# szu-etep-stc89c52rc-2024.net
KiCad netlist of a schematic drawn in EasyEDA Pro
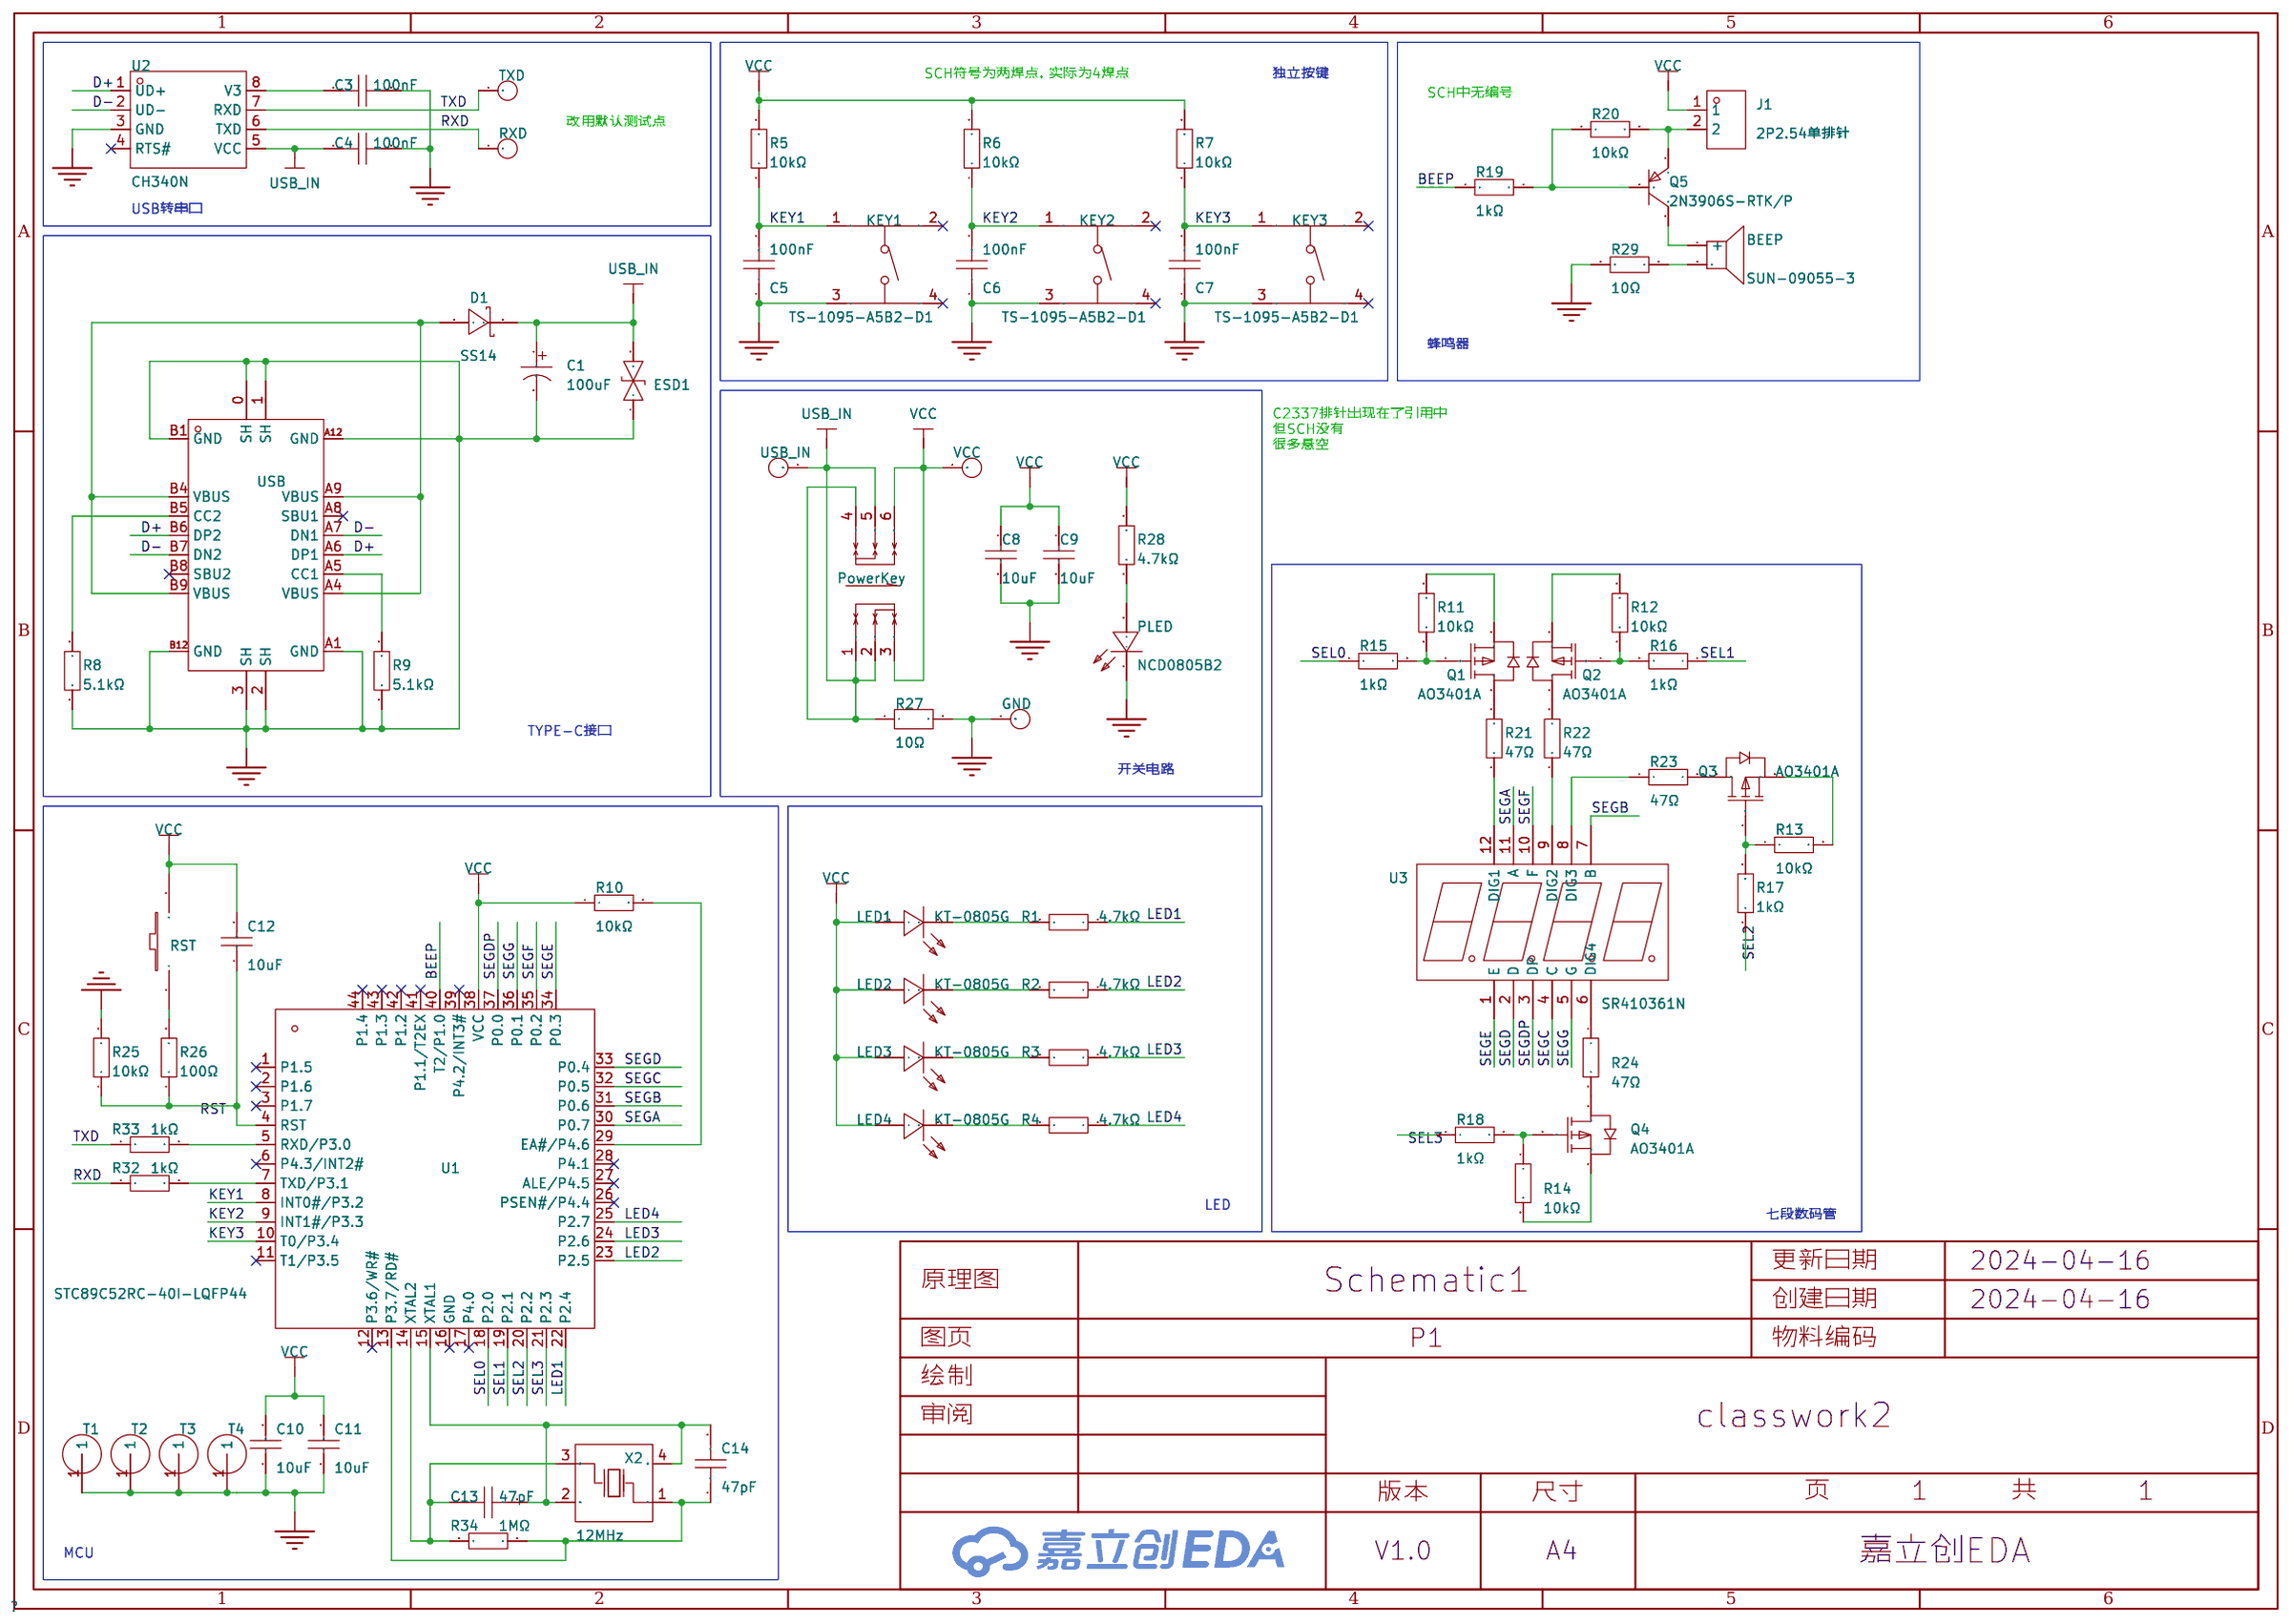
[diagram p0: schematic sheet]

(export (version "E")
  (design (tool "Eeschema 10.0.6"))
  (components
    (comp (ref "BEEP")
      (value "SUN-09055-3")
      (footprint "easyedapro:BUZ-TH_BD9.0-P5.00-D0.6-FD")
      (description "频率2800+300Hz,1.5-5V电压驱动")
      (libsource (lib "easyedapro") (part "SUN-09055-3"))
    )
    (comp (ref "C1")
      (value "100uF")
      (footprint "easyedapro:CAP-TH_BD5.0-P2.00-D0.8-FD")
      (description "容值:100uF;精度:±20%;额定电压:16V;纹波电流:-;等效串联电阻:-;")
      (fields
        (field (name "Manufacturer Part") "KS107M016D07RR0VH2FP0")
        (field (name "Manufacturer") "CX(承兴)")
      )
      (libsource (lib "easyedapro") (part "100uF 16V 5*7"))
    )
    (comp (ref "C3")
      (value "100nF")
      (footprint "easyedapro:C0603")
      (description "容值:100nF;精度:±10%;额定电压:50V;材质(温度系数):X7R;")
      (fields
        (field (name "Manufacturer Part") "CC0603KRX7R9BB104")
        (field (name "Manufacturer") "YAGEO(国巨)")
      )
      (libsource (lib "easyedapro") (part "CC0603KRX7R9BB104"))
    )
    (comp (ref "C4")
      (value "100nF")
      (footprint "easyedapro:C0603")
      (description "容值:100nF;精度:±10%;额定电压:50V;材质(温度系数):X7R;")
      (fields
        (field (name "Manufacturer Part") "CC0603KRX7R9BB104")
        (field (name "Manufacturer") "YAGEO(国巨)")
      )
      (libsource (lib "easyedapro") (part "CC0603KRX7R9BB104"))
    )
    (comp (ref "C5")
      (value "100nF")
      (footprint "easyedapro:C0603")
      (description "容值:100nF;精度:±10%;额定电压:50V;材质(温度系数):X7R;")
      (fields
        (field (name "Manufacturer Part") "CC0603KRX7R9BB104")
        (field (name "Manufacturer") "YAGEO(国巨)")
      )
      (libsource (lib "easyedapro") (part "CC0603KRX7R9BB104"))
    )
    (comp (ref "C6")
      (value "100nF")
      (footprint "easyedapro:C0603")
      (description "容值:100nF;精度:±10%;额定电压:50V;材质(温度系数):X7R;")
      (fields
        (field (name "Manufacturer Part") "CC0603KRX7R9BB104")
        (field (name "Manufacturer") "YAGEO(国巨)")
      )
      (libsource (lib "easyedapro") (part "CC0603KRX7R9BB104"))
    )
    (comp (ref "C7")
      (value "100nF")
      (footprint "easyedapro:C0603")
      (description "容值:100nF;精度:±10%;额定电压:50V;材质(温度系数):X7R;")
      (fields
        (field (name "Manufacturer Part") "CC0603KRX7R9BB104")
        (field (name "Manufacturer") "YAGEO(国巨)")
      )
      (libsource (lib "easyedapro") (part "CC0603KRX7R9BB104"))
    )
    (comp (ref "C8")
      (value "10uF")
      (footprint "easyedapro:C0603")
      (description "容值:10uF;精度:±10%;额定电压:16V;材质(温度系数):X5R;")
      (fields (field (name "Manufacturer Part") "0603X106K160NT") (field (name "Manufacturer") "FH(风华)"))
      (libsource (lib "easyedapro") (part "0603X106K160NT"))
    )
    (comp (ref "C9")
      (value "10uF")
      (footprint "easyedapro:C0603")
      (description "容值:10uF;精度:±10%;额定电压:16V;材质(温度系数):X5R;")
      (fields (field (name "Manufacturer Part") "0603X106K160NT") (field (name "Manufacturer") "FH(风华)"))
      (libsource (lib "easyedapro") (part "0603X106K160NT"))
    )
    (comp (ref "C10")
      (value "10uF")
      (footprint "easyedapro:C0603")
      (description "容值:10uF;精度:±10%;额定电压:16V;材质(温度系数):X5R;")
      (fields (field (name "Manufacturer Part") "0603X106K160NT") (field (name "Manufacturer") "FH(风华)"))
      (libsource (lib "easyedapro") (part "0603X106K160NT"))
    )
    (comp (ref "C11")
      (value "10uF")
      (footprint "easyedapro:C0603")
      (description "容值:10uF;精度:±10%;额定电压:16V;材质(温度系数):X5R;")
      (fields (field (name "Manufacturer Part") "0603X106K160NT") (field (name "Manufacturer") "FH(风华)"))
      (libsource (lib "easyedapro") (part "0603X106K160NT"))
    )
    (comp (ref "C12")
      (value "10uF")
      (footprint "easyedapro:C0603")
      (description "容值:10uF;精度:±10%;额定电压:16V;材质(温度系数):X5R;")
      (fields (field (name "Manufacturer Part") "0603X106K160NT") (field (name "Manufacturer") "FH(风华)"))
      (libsource (lib "easyedapro") (part "0603X106K160NT"))
    )
    (comp (ref "C13")
      (value "47pF")
      (footprint "easyedapro:C0603")
      (description "容值:47pF;精度:±5%;额定电压:100V;材质(温度系数):C0G;")
      (fields
        (field (name "Manufacturer Part") "CL10C470JC8NNNC")
        (field (name "Manufacturer") "SAMSUNG(三星)")
      )
      (libsource (lib "easyedapro") (part "CL10C470JC8NNNC"))
    )
    (comp (ref "C14")
      (value "47pF")
      (footprint "easyedapro:C0603")
      (description "容值:47pF;精度:±5%;额定电压:100V;材质(温度系数):C0G;")
      (fields
        (field (name "Manufacturer Part") "CL10C470JC8NNNC")
        (field (name "Manufacturer") "SAMSUNG(三星)")
      )
      (libsource (lib "easyedapro") (part "CL10C470JC8NNNC"))
    )
    (comp (ref "D1")
      (value "SS14")
      (footprint "easyedapro:SMA_L4.3-W2.6-LS5.2-RD")
      (description "正向压降(Vf):550mV@1A;直流反向耐压(Vr):40V;平均整流电流(Io):1A;")
      (fields (field (name "Manufacturer") "星海"))
      (libsource (lib "easyedapro") (part "SS14_C84343"))
    )
    (comp (ref "ESD1")
      (value "0603ESDA-05N")
      (footprint "easyedapro:D0603-BI")
      (description "极性:双向;反向截止电压(Vrwm):5V;最大钳位电压:50V;")
      (fields (field (name "Manufacturer") "BORN(伯恩半导体)"))
      (libsource (lib "easyedapro") (part "0603ESDA-05N"))
    )
    (comp (ref "GND")
      (value "~")
      (footprint "easyedapro:测试点0.9mm")
      (libsource (lib "easyedapro") (part "测试点0.9mm"))
    )
    (comp (ref "J1")
      (value "2P2.54单排针")
      (footprint "easyedapro:HDR-TH_2P-P2.54-V-M")
      (libsource (lib "easyedapro") (part "2P2.54单排针"))
    )
    (comp (ref "KEY1")
      (value "TS-1095-A5B2-D1")
      (footprint "easyedapro:SW-TH_4P-L6.0-W6.0-P4.50-LS6.5")
      (description "电路结构:单刀单掷;按钮形状:圆形按钮;作用力:180gf;安装方式:直插;开关长度:6mm;开关宽度:6mm;开关高度:6mm;带支架:不带;机械寿命:-;")
      (fields (field (name "Manufacturer") "Yuandi(元迪)"))
      (libsource (lib "easyedapro") (part "TS-1095-A5B2-D1"))
    )
    (comp (ref "KEY2")
      (value "TS-1095-A5B2-D1")
      (footprint "easyedapro:SW-TH_4P-L6.0-W6.0-P4.50-LS6.5")
      (description "电路结构:单刀单掷;按钮形状:圆形按钮;作用力:180gf;安装方式:直插;开关长度:6mm;开关宽度:6mm;开关高度:6mm;带支架:不带;机械寿命:-;")
      (fields (field (name "Manufacturer") "Yuandi(元迪)"))
      (libsource (lib "easyedapro") (part "TS-1095-A5B2-D1"))
    )
    (comp (ref "KEY3")
      (value "TS-1095-A5B2-D1")
      (footprint "easyedapro:SW-TH_4P-L6.0-W6.0-P4.50-LS6.5")
      (description "电路结构:单刀单掷;按钮形状:圆形按钮;作用力:180gf;安装方式:直插;开关长度:6mm;开关宽度:6mm;开关高度:6mm;带支架:不带;机械寿命:-;")
      (fields (field (name "Manufacturer") "Yuandi(元迪)"))
      (libsource (lib "easyedapro") (part "TS-1095-A5B2-D1"))
    )
    (comp (ref "LED1")
      (value "KT-0805G")
      (footprint "easyedapro:LED0805-R-RD")
      (description "灯头类型:-;发光颜色:翠绿色;正向电压(VF):-;功率:-;正向电流:-;主波长:-;二极管配置:-;透镜颜色:-;色温:-;发光强度:-;发光角度:-;载带方式:-;工作温度:-;")
      (fields (field (name "Manufacturer") "KENTO"))
      (libsource (lib "easyedapro") (part "0805G (Green)"))
    )
    (comp (ref "LED2")
      (value "KT-0805G")
      (footprint "easyedapro:LED0805-R-RD")
      (description "灯头类型:-;发光颜色:翠绿色;正向电压(VF):-;功率:-;正向电流:-;主波长:-;二极管配置:-;透镜颜色:-;色温:-;发光强度:-;发光角度:-;载带方式:-;工作温度:-;")
      (fields (field (name "Manufacturer") "KENTO"))
      (libsource (lib "easyedapro") (part "0805G (Green)"))
    )
    (comp (ref "LED3")
      (value "KT-0805G")
      (footprint "easyedapro:LED0805-R-RD")
      (description "灯头类型:-;发光颜色:翠绿色;正向电压(VF):-;功率:-;正向电流:-;主波长:-;二极管配置:-;透镜颜色:-;色温:-;发光强度:-;发光角度:-;载带方式:-;工作温度:-;")
      (fields (field (name "Manufacturer") "KENTO"))
      (libsource (lib "easyedapro") (part "0805G (Green)"))
    )
    (comp (ref "LED4")
      (value "KT-0805G")
      (footprint "easyedapro:LED0805-R-RD")
      (description "灯头类型:-;发光颜色:翠绿色;正向电压(VF):-;功率:-;正向电流:-;主波长:-;二极管配置:-;透镜颜色:-;色温:-;发光强度:-;发光角度:-;载带方式:-;工作温度:-;")
      (fields (field (name "Manufacturer") "KENTO"))
      (libsource (lib "easyedapro") (part "0805G (Green)"))
    )
    (comp (ref "PLED")
      (value "NCD0805B2")
      (footprint "easyedapro:LED0805-R-RD")
      (fields (field (name "Manufacturer") "国星光电"))
      (libsource (lib "easyedapro") (part "FC-A2012BK-470H2"))
    )
    (comp (ref "PowerKey")
      (value "XKB8080-Z")
      (footprint "easyedapro:SW-TH_6P-L8.0-W8.0-P2.50")
      (description "自锁/无锁:自锁;安装方式:直插;触点电流:100mA;额定电压 (AC):250V;额定电压 (DC):30V;带灯:不带;作用力:160gf;机械寿命:10万次;")
      (fields (field (name "Manufacturer") "XKB Connectivity(中国星坤)"))
      (libsource (lib "easyedapro") (part "XKB8080-Z"))
    )
    (comp (ref "Q1")
      (value "AO3401A")
      (footprint "easyedapro:SOT-23_L2.9-W1.3-P1.90-LS2.4-BR")
      (fields (field (name "Manufacturer") "AOS"))
      (libsource (lib "easyedapro") (part "AO3401A"))
    )
    (comp (ref "Q2")
      (value "AO3401A")
      (footprint "easyedapro:SOT-23_L2.9-W1.3-P1.90-LS2.4-BR")
      (fields (field (name "Manufacturer") "AOS"))
      (libsource (lib "easyedapro") (part "AO3401A"))
    )
    (comp (ref "Q3")
      (value "AO3401A")
      (footprint "easyedapro:SOT-23_L2.9-W1.3-P1.90-LS2.4-BR")
      (fields (field (name "Manufacturer") "AOS"))
      (libsource (lib "easyedapro") (part "AO3401A"))
    )
    (comp (ref "Q4")
      (value "AO3401A")
      (footprint "easyedapro:SOT-23_L2.9-W1.3-P1.90-LS2.4-BR")
      (fields (field (name "Manufacturer") "AOS"))
      (libsource (lib "easyedapro") (part "AO3401A"))
    )
    (comp (ref "Q5")
      (value "2N3906S-RTK/P")
      (footprint "easyedapro:SOT-23-3_L2.9-W1.6-P1.90-LS2.8-TR-CW")
      (description "晶体管类型:PNP;集电极电流(Ic):200mA;集射极击穿电压(Vceo):40V;功率(Pd):350mW;直流电流增益(hFE@Ic,Vce):100@10mA,1V;")
      (fields (field (name "Manufacturer") "KEC"))
      (libsource (lib "easyedapro") (part "2N3906S-RTK/PS"))
    )
    (comp (ref "R1")
      (value "4.7kΩ")
      (footprint "easyedapro:R0603")
      (description "电阻类型:厚膜电阻;阻值:4.7kΩ;精度:±1%;功率:100mW;最大工作电压:75V;温度系数:±100ppm/°C;")
      (fields
        (field (name "Manufacturer Part") "0603WAF4701T5E")
        (field (name "Manufacturer") "UNI-ROYAL(厚声)")
      )
      (libsource (lib "easyedapro") (part "0603WAF4701T5E"))
    )
    (comp (ref "R2")
      (value "4.7kΩ")
      (footprint "easyedapro:R0603")
      (description "电阻类型:厚膜电阻;阻值:4.7kΩ;精度:±1%;功率:100mW;最大工作电压:75V;温度系数:±100ppm/°C;")
      (fields
        (field (name "Manufacturer Part") "0603WAF4701T5E")
        (field (name "Manufacturer") "UNI-ROYAL(厚声)")
      )
      (libsource (lib "easyedapro") (part "0603WAF4701T5E"))
    )
    (comp (ref "R3")
      (value "4.7kΩ")
      (footprint "easyedapro:R0603")
      (description "电阻类型:厚膜电阻;阻值:4.7kΩ;精度:±1%;功率:100mW;最大工作电压:75V;温度系数:±100ppm/°C;")
      (fields
        (field (name "Manufacturer Part") "0603WAF4701T5E")
        (field (name "Manufacturer") "UNI-ROYAL(厚声)")
      )
      (libsource (lib "easyedapro") (part "0603WAF4701T5E"))
    )
    (comp (ref "R4")
      (value "4.7kΩ")
      (footprint "easyedapro:R0603")
      (description "电阻类型:厚膜电阻;阻值:4.7kΩ;精度:±1%;功率:100mW;最大工作电压:75V;温度系数:±100ppm/°C;")
      (fields
        (field (name "Manufacturer Part") "0603WAF4701T5E")
        (field (name "Manufacturer") "UNI-ROYAL(厚声)")
      )
      (libsource (lib "easyedapro") (part "0603WAF4701T5E"))
    )
    (comp (ref "R5")
      (value "10kΩ")
      (footprint "easyedapro:R0402")
      (description "电阻类型:厚膜电阻;阻值:10kΩ;精度:±1%;功率:62.5mW;最大工作电压:50V;温度系数:±100ppm/°C;")
      (fields
        (field (name "Manufacturer Part") "0402WGF1002TCE")
        (field (name "Manufacturer") "UNI-ROYAL(厚声)")
      )
      (libsource (lib "easyedapro") (part "0402WGF1002TCE"))
    )
    (comp (ref "R6")
      (value "10kΩ")
      (footprint "easyedapro:R0402")
      (description "电阻类型:厚膜电阻;阻值:10kΩ;精度:±1%;功率:62.5mW;最大工作电压:50V;温度系数:±100ppm/°C;")
      (fields
        (field (name "Manufacturer Part") "0402WGF1002TCE")
        (field (name "Manufacturer") "UNI-ROYAL(厚声)")
      )
      (libsource (lib "easyedapro") (part "0402WGF1002TCE"))
    )
    (comp (ref "R7")
      (value "10kΩ")
      (footprint "easyedapro:R0402")
      (description "电阻类型:厚膜电阻;阻值:10kΩ;精度:±1%;功率:62.5mW;最大工作电压:50V;温度系数:±100ppm/°C;")
      (fields
        (field (name "Manufacturer Part") "0402WGF1002TCE")
        (field (name "Manufacturer") "UNI-ROYAL(厚声)")
      )
      (libsource (lib "easyedapro") (part "0402WGF1002TCE"))
    )
    (comp (ref "R8")
      (value "5.1kΩ")
      (footprint "easyedapro:R0603")
      (description "电阻类型:厚膜电阻;阻值:5.1kΩ;精度:±1%;功率:100mW;最大工作电压:75V;温度系数:±100ppm/°C;")
      (fields
        (field (name "Manufacturer Part") "0603WAF5101T5E")
        (field (name "Manufacturer") "UNI-ROYAL(厚声)")
      )
      (libsource (lib "easyedapro") (part "0603WAF5101T5E"))
    )
    (comp (ref "R9")
      (value "5.1kΩ")
      (footprint "easyedapro:R0603")
      (description "电阻类型:厚膜电阻;阻值:5.1kΩ;精度:±1%;功率:100mW;最大工作电压:75V;温度系数:±100ppm/°C;")
      (fields
        (field (name "Manufacturer Part") "0603WAF5101T5E")
        (field (name "Manufacturer") "UNI-ROYAL(厚声)")
      )
      (libsource (lib "easyedapro") (part "0603WAF5101T5E"))
    )
    (comp (ref "R10")
      (value "10kΩ")
      (footprint "easyedapro:R0402")
      (description "电阻类型:厚膜电阻;阻值:10kΩ;精度:±1%;功率:62.5mW;最大工作电压:50V;温度系数:±100ppm/°C;")
      (fields
        (field (name "Manufacturer Part") "0402WGF1002TCE")
        (field (name "Manufacturer") "UNI-ROYAL(厚声)")
      )
      (libsource (lib "easyedapro") (part "0402WGF1002TCE"))
    )
    (comp (ref "R11")
      (value "10kΩ")
      (footprint "easyedapro:R0603")
      (description "电阻类型:厚膜电阻;阻值:10kΩ;精度:±1%;功率:100mW;最大工作电压:75V;温度系数:±100ppm/°C;")
      (fields
        (field (name "Manufacturer Part") "0603WAF1002T5E")
        (field (name "Manufacturer") "UNI-ROYAL(厚声)")
      )
      (libsource (lib "easyedapro") (part "0603WAF1002T5E"))
    )
    (comp (ref "R12")
      (value "10kΩ")
      (footprint "easyedapro:R0603")
      (description "电阻类型:厚膜电阻;阻值:10kΩ;精度:±1%;功率:100mW;最大工作电压:75V;温度系数:±100ppm/°C;")
      (fields
        (field (name "Manufacturer Part") "0603WAF1002T5E")
        (field (name "Manufacturer") "UNI-ROYAL(厚声)")
      )
      (libsource (lib "easyedapro") (part "0603WAF1002T5E"))
    )
    (comp (ref "R13")
      (value "10kΩ")
      (footprint "easyedapro:R0603")
      (description "电阻类型:厚膜电阻;阻值:10kΩ;精度:±1%;功率:100mW;最大工作电压:75V;温度系数:±100ppm/°C;")
      (fields
        (field (name "Manufacturer Part") "0603WAF1002T5E")
        (field (name "Manufacturer") "UNI-ROYAL(厚声)")
      )
      (libsource (lib "easyedapro") (part "0603WAF1002T5E"))
    )
    (comp (ref "R14")
      (value "10kΩ")
      (footprint "easyedapro:R0603")
      (description "电阻类型:厚膜电阻;阻值:10kΩ;精度:±1%;功率:100mW;最大工作电压:75V;温度系数:±100ppm/°C;")
      (fields
        (field (name "Manufacturer Part") "0603WAF1002T5E")
        (field (name "Manufacturer") "UNI-ROYAL(厚声)")
      )
      (libsource (lib "easyedapro") (part "0603WAF1002T5E"))
    )
    (comp (ref "R15")
      (value "1kΩ")
      (footprint "easyedapro:R0603")
      (description "电阻类型:厚膜电阻;阻值:1kΩ;精度:±1%;功率:100mW;最大工作电压:75V;温度系数:±100ppm/°C;")
      (fields
        (field (name "Manufacturer Part") "0603WAF1001T5E")
        (field (name "Manufacturer") "UNI-ROYAL(厚声)")
      )
      (libsource (lib "easyedapro") (part "0603WAF1001T5E"))
    )
    (comp (ref "R16")
      (value "1kΩ")
      (footprint "easyedapro:R0603")
      (description "电阻类型:厚膜电阻;阻值:1kΩ;精度:±1%;功率:100mW;最大工作电压:75V;温度系数:±100ppm/°C;")
      (fields
        (field (name "Manufacturer Part") "0603WAF1001T5E")
        (field (name "Manufacturer") "UNI-ROYAL(厚声)")
      )
      (libsource (lib "easyedapro") (part "0603WAF1001T5E"))
    )
    (comp (ref "R17")
      (value "1kΩ")
      (footprint "easyedapro:R0603")
      (description "电阻类型:厚膜电阻;阻值:1kΩ;精度:±1%;功率:100mW;最大工作电压:75V;温度系数:±100ppm/°C;")
      (fields
        (field (name "Manufacturer Part") "0603WAF1001T5E")
        (field (name "Manufacturer") "UNI-ROYAL(厚声)")
      )
      (libsource (lib "easyedapro") (part "0603WAF1001T5E"))
    )
    (comp (ref "R18")
      (value "1kΩ")
      (footprint "easyedapro:R0603")
      (description "电阻类型:厚膜电阻;阻值:1kΩ;精度:±1%;功率:100mW;最大工作电压:75V;温度系数:±100ppm/°C;")
      (fields
        (field (name "Manufacturer Part") "0603WAF1001T5E")
        (field (name "Manufacturer") "UNI-ROYAL(厚声)")
      )
      (libsource (lib "easyedapro") (part "0603WAF1001T5E"))
    )
    (comp (ref "R19")
      (value "1kΩ")
      (footprint "easyedapro:R0603")
      (description "电阻类型:厚膜电阻;阻值:1kΩ;精度:±1%;功率:100mW;最大工作电压:75V;温度系数:±100ppm/°C;")
      (fields
        (field (name "Manufacturer Part") "0603WAF1001T5E")
        (field (name "Manufacturer") "UNI-ROYAL(厚声)")
      )
      (libsource (lib "easyedapro") (part "0603WAF1001T5E"))
    )
    (comp (ref "R20")
      (value "10kΩ")
      (footprint "easyedapro:R0603")
      (description "电阻类型:厚膜电阻;阻值:10kΩ;精度:±1%;功率:100mW;最大工作电压:75V;温度系数:±100ppm/°C;")
      (fields
        (field (name "Manufacturer Part") "0603WAF1002T5E")
        (field (name "Manufacturer") "UNI-ROYAL(厚声)")
      )
      (libsource (lib "easyedapro") (part "0603WAF1002T5E"))
    )
    (comp (ref "R21")
      (value "47Ω")
      (footprint "easyedapro:R0603")
      (description "电阻类型:厚膜电阻;阻值:47Ω;精度:±1%;功率:100mW;最大工作电压:75V;温度系数:±100ppm/°C;")
      (fields
        (field (name "Manufacturer Part") "0603WAF470JT5E")
        (field (name "Manufacturer") "UNI-ROYAL(厚声)")
      )
      (libsource (lib "easyedapro") (part "0603WAF470JT5E"))
    )
    (comp (ref "R22")
      (value "47Ω")
      (footprint "easyedapro:R0603")
      (description "电阻类型:厚膜电阻;阻值:47Ω;精度:±1%;功率:100mW;最大工作电压:75V;温度系数:±100ppm/°C;")
      (fields
        (field (name "Manufacturer Part") "0603WAF470JT5E")
        (field (name "Manufacturer") "UNI-ROYAL(厚声)")
      )
      (libsource (lib "easyedapro") (part "0603WAF470JT5E"))
    )
    (comp (ref "R23")
      (value "47Ω")
      (footprint "easyedapro:R0603")
      (description "电阻类型:厚膜电阻;阻值:47Ω;精度:±1%;功率:100mW;最大工作电压:75V;温度系数:±100ppm/°C;")
      (fields
        (field (name "Manufacturer Part") "0603WAF470JT5E")
        (field (name "Manufacturer") "UNI-ROYAL(厚声)")
      )
      (libsource (lib "easyedapro") (part "0603WAF470JT5E"))
    )
    (comp (ref "R24")
      (value "47Ω")
      (footprint "easyedapro:R0603")
      (description "电阻类型:厚膜电阻;阻值:47Ω;精度:±1%;功率:100mW;最大工作电压:75V;温度系数:±100ppm/°C;")
      (fields
        (field (name "Manufacturer Part") "0603WAF470JT5E")
        (field (name "Manufacturer") "UNI-ROYAL(厚声)")
      )
      (libsource (lib "easyedapro") (part "0603WAF470JT5E"))
    )
    (comp (ref "R25")
      (value "10kΩ")
      (footprint "easyedapro:R0402")
      (description "电阻类型:厚膜电阻;阻值:10kΩ;精度:±1%;功率:62.5mW;最大工作电压:50V;温度系数:±100ppm/°C;")
      (fields
        (field (name "Manufacturer Part") "0402WGF1002TCE")
        (field (name "Manufacturer") "UNI-ROYAL(厚声)")
      )
      (libsource (lib "easyedapro") (part "0402WGF1002TCE"))
    )
    (comp (ref "R26")
      (value "100Ω")
      (footprint "easyedapro:R0603")
      (description "电阻类型:厚膜电阻;阻值:100Ω;精度:±1%;功率:100mW;最大工作电压:75V;温度系数:±200ppm/°C;")
      (fields
        (field (name "Manufacturer Part") "0603WAF1000T5E")
        (field (name "Manufacturer") "UNI-ROYAL(厚声)")
      )
      (libsource (lib "easyedapro") (part "0603WAF1000T5E"))
    )
    (comp (ref "R27")
      (value "10Ω")
      (footprint "easyedapro:R1206")
      (description "电阻类型:厚膜电阻;阻值:10Ω;精度:±10%;功率:600mW;最大工作电压:200V;温度系数:±400ppm/°C;")
      (fields
        (field (name "Manufacturer Part") "AS0606K0100T5E")
        (field (name "Manufacturer") "UNI-ROYAL(厚声)")
      )
      (libsource (lib "easyedapro") (part "AS0606K0100T5E"))
    )
    (comp (ref "R28")
      (value "4.7kΩ")
      (footprint "easyedapro:R0603")
      (description "电阻类型:厚膜电阻;阻值:4.7kΩ;精度:±1%;功率:100mW;最大工作电压:75V;温度系数:±100ppm/°C;")
      (fields
        (field (name "Manufacturer Part") "0603WAF4701T5E")
        (field (name "Manufacturer") "UNI-ROYAL(厚声)")
      )
      (libsource (lib "easyedapro") (part "0603WAF4701T5E"))
    )
    (comp (ref "R29")
      (value "10Ω")
      (footprint "easyedapro:R0603")
      (description "电阻类型:厚膜电阻;阻值:10Ω;精度:±1%;功率:100mW;最大工作电压:75V;温度系数:±400ppm/°C;")
      (fields
        (field (name "Manufacturer Part") "0603WAF100JT5E")
        (field (name "Manufacturer") "UNI-ROYAL(厚声)")
      )
      (libsource (lib "easyedapro") (part "0603WAF100JT5E"))
    )
    (comp (ref "R32")
      (value "1kΩ")
      (footprint "easyedapro:R0603")
      (description "电阻类型:厚膜电阻;阻值:1kΩ;精度:±1%;功率:100mW;最大工作电压:75V;温度系数:±100ppm/°C;")
      (fields
        (field (name "Manufacturer Part") "0603WAF1001T5E")
        (field (name "Manufacturer") "UNI-ROYAL(厚声)")
      )
      (libsource (lib "easyedapro") (part "0603WAF1001T5E"))
    )
    (comp (ref "R33")
      (value "1kΩ")
      (footprint "easyedapro:R0603")
      (description "电阻类型:厚膜电阻;阻值:1kΩ;精度:±1%;功率:100mW;最大工作电压:75V;温度系数:±100ppm/°C;")
      (fields
        (field (name "Manufacturer Part") "0603WAF1001T5E")
        (field (name "Manufacturer") "UNI-ROYAL(厚声)")
      )
      (libsource (lib "easyedapro") (part "0603WAF1001T5E"))
    )
    (comp (ref "R34")
      (value "1MΩ")
      (footprint "easyedapro:R0603")
      (description "电阻类型:厚膜电阻;阻值:1MΩ;精度:±1%;功率:100mW;最大工作电压:75V;温度系数:±100ppm/°C;")
      (fields
        (field (name "Manufacturer Part") "0603WAF1004T5E")
        (field (name "Manufacturer") "UNI-ROYAL(厚声)")
      )
      (libsource (lib "easyedapro") (part "0603WAF1004T5E"))
    )
    (comp (ref "RST")
      (value "轻触开关,3*6*2.5塑头白色,260G,行程0.25mm,贴片 (SMT业务专用)")
      (footprint "easyedapro:SW-SMD_L6.1-W3.6-LS8.0")
      (libsource (lib "easyedapro") (part "Switch,3*6*2.5Plastic head white,260G, 0.25mm,SMD"))
    )
    (comp (ref "RXD")
      (value "~")
      (footprint "easyedapro:测试点0.9mm")
      (libsource (lib "easyedapro") (part "测试点0.9mm"))
    )
    (comp (ref "T1") (value "~") (footprint "easyedapro:M3定位孔") (libsource (lib "easyedapro") (part "M3定位孔")))
    (comp (ref "T2") (value "~") (footprint "easyedapro:M3定位孔") (libsource (lib "easyedapro") (part "M3定位孔")))
    (comp (ref "T3") (value "~") (footprint "easyedapro:M3定位孔") (libsource (lib "easyedapro") (part "M3定位孔")))
    (comp (ref "T4") (value "~") (footprint "easyedapro:M3定位孔") (libsource (lib "easyedapro") (part "M3定位孔")))
    (comp (ref "TXD")
      (value "~")
      (footprint "easyedapro:测试点0.9mm")
      (libsource (lib "easyedapro") (part "测试点0.9mm"))
    )
    (comp (ref "U1")
      (value "STC89C52RC-40I-LQFP44")
      (footprint "easyedapro:LQFP-44_L10.0-W10.0-P0.80-LS12.0-BL")
      (description "CPU内核:51系列;程序存储容量:8KB;RAM总容量:512Byte;GPIO端口数量:39;工作电压范围:3.3V~5.5V;CPU最大主频:-;程序存储器类型:FLASH;")
      (fields (field (name "Manufacturer") "STC(宏晶)"))
      (libsource (lib "easyedapro") (part "STC89C52RC-40I_C8707"))
    )
    (comp (ref "U2")
      (value "CH340N")
      (footprint "easyedapro:SOP-8_L5.0-W4.0-P1.27-LS6.0-BL")
      (description "应用功能:-;接口协议:-;")
      (fields (field (name "Manufacturer") "WCH(南京沁恒)"))
      (libsource (lib "easyedapro") (part "CH340N"))
    )
    (comp (ref "U3")
      (value "SR410361N")
      (footprint "easyedapro:LED-SEG-TH_12P-L30.0-W14.0-P2.54-S10.26-BL")
      (description "数码管位数:4位;发光颜色:红色;LED极性:共阳极;数字/字母大小(英寸):0.36;")
      (fields (field (name "Manufacturer") "ARKLED(方舟)"))
      (libsource (lib "easyedapro") (part "SR410361N"))
    )
    (comp (ref "USB")
      (value "TYPE-C-31-M-12")
      (footprint "easyedapro:USB-C_SMD-TYPE-C-31-M-12")
      (description "连接器类型:Type-C;标准:-;公母:母;端口数量:1;触点数量:16P;安装方式:-;额定电流 - 电源:5A;触头材质:-;触头镀层:-;工作温度范围:-;焊接温度(最大值):-;")
      (fields (field (name "Manufacturer") "韩国韩荣"))
      (libsource (lib "easyedapro") (part "TYPE-C-31-M-12"))
    )
    (comp (ref "USB_IN")
      (value "~")
      (footprint "easyedapro:测试点0.9mm")
      (libsource (lib "easyedapro") (part "测试点0.9mm"))
    )
    (comp (ref "VCC")
      (value "~")
      (footprint "easyedapro:测试点0.9mm")
      (libsource (lib "easyedapro") (part "测试点0.9mm"))
    )
    (comp (ref "X2")
      (value "12MHz")
      (footprint "easyedapro:OSC-SMD_4P-L3.2-W2.5-BL")
      (description "晶振类型:贴片晶振;频率:12MHz;常温频差:±10ppm;外接负载电容:20pF;频率稳定度(全温):±20ppm;")
      (fields (field (name "Manufacturer Part") "X322512MSB4SI") (field (name "Manufacturer") "YXC(扬兴晶振)"))
      (libsource (lib "easyedapro") (part "X322512MSB4SI"))
    )
  )
  (nets
    (net (code "1") (name "/BEEP") (class "Default")
      (node (ref "R19") (pin "1") (pinfunction "1_1") (pintype "input"))
      (node (ref "U1") (pin "40") (pinfunction "T2/P1.0_40") (pintype "unspecified"))
    )
    (net (code "2") (name "/D+") (class "Default")
      (node (ref "U2") (pin "1") (pinfunction "UD+_1") (pintype "unspecified"))
      (node (ref "USB") (pin "A6") (pinfunction "DP1_A6") (pintype "unspecified"))
      (node (ref "USB") (pin "B6") (pinfunction "DP2_B6") (pintype "unspecified"))
    )
    (net (code "3") (name "/D-") (class "Default")
      (node (ref "U2") (pin "2") (pinfunction "UD-_2") (pintype "unspecified"))
      (node (ref "USB") (pin "A7") (pinfunction "DN1_A7") (pintype "unspecified"))
      (node (ref "USB") (pin "B7") (pinfunction "DN2_B7") (pintype "unspecified"))
    )
    (net (code "4") (name "/KEY1") (class "Default")
      (node (ref "C5") (pin "2") (pinfunction "2_2") (pintype "unspecified"))
      (node (ref "KEY1") (pin "1") (pinfunction "1_1") (pintype "input"))
      (node (ref "R5") (pin "1") (pinfunction "1_1") (pintype "input"))
      (node (ref "U1") (pin "8") (pinfunction "INT0#/P3.2_8") (pintype "unspecified"))
    )
    (net (code "5") (name "/KEY2") (class "Default")
      (node (ref "C6") (pin "2") (pinfunction "2_2") (pintype "unspecified"))
      (node (ref "KEY2") (pin "1") (pinfunction "1_1") (pintype "input"))
      (node (ref "R6") (pin "1") (pinfunction "1_1") (pintype "input"))
      (node (ref "U1") (pin "9") (pinfunction "INT1#/P3.3_9") (pintype "unspecified"))
    )
    (net (code "6") (name "/KEY3") (class "Default")
      (node (ref "C7") (pin "2") (pinfunction "2_2") (pintype "unspecified"))
      (node (ref "KEY3") (pin "1") (pinfunction "1_1") (pintype "input"))
      (node (ref "R7") (pin "1") (pinfunction "1_1") (pintype "input"))
      (node (ref "U1") (pin "10") (pinfunction "T0/P3.4_10") (pintype "unspecified"))
    )
    (net (code "7") (name "/LED1") (class "Default")
      (node (ref "R1") (pin "1") (pinfunction "1_1") (pintype "input"))
      (node (ref "U1") (pin "22") (pinfunction "P2.4_22") (pintype "unspecified"))
    )
    (net (code "8") (name "/LED2") (class "Default")
      (node (ref "R2") (pin "1") (pinfunction "1_1") (pintype "input"))
      (node (ref "U1") (pin "23") (pinfunction "P2.5_23") (pintype "unspecified"))
    )
    (net (code "9") (name "/LED3") (class "Default")
      (node (ref "R3") (pin "1") (pinfunction "1_1") (pintype "input"))
      (node (ref "U1") (pin "24") (pinfunction "P2.6_24") (pintype "unspecified"))
    )
    (net (code "10") (name "/LED4") (class "Default")
      (node (ref "R4") (pin "1") (pinfunction "1_1") (pintype "input"))
      (node (ref "U1") (pin "25") (pinfunction "P2.7_25") (pintype "unspecified"))
    )
    (net (code "11") (name "/RST") (class "Default")
      (node (ref "C12") (pin "1") (pinfunction "1_1") (pintype "input"))
      (node (ref "R25") (pin "1") (pinfunction "1_1") (pintype "input"))
      (node (ref "R26") (pin "1") (pinfunction "1_1") (pintype "input"))
      (node (ref "U1") (pin "4") (pinfunction "RST_4") (pintype "unspecified"))
    )
    (net (code "12") (name "/RXD") (class "Default")
      (node (ref "R32") (pin "1") (pinfunction "1_1") (pintype "input"))
      (node (ref "RXD") (pin "1") (pinfunction "Pin1_1") (pintype "input"))
      (node (ref "U2") (pin "6") (pinfunction "TXD_6") (pintype "unspecified"))
    )
    (net (code "13") (name "/SEGA") (class "Default")
      (node (ref "U1") (pin "30") (pinfunction "P0.7_30") (pintype "unspecified"))
      (node (ref "U3") (pin "11") (pinfunction "A_11") (pintype "input"))
    )
    (net (code "14") (name "/SEGB") (class "Default")
      (node (ref "U1") (pin "31") (pinfunction "P0.6_31") (pintype "unspecified"))
      (node (ref "U3") (pin "7") (pinfunction "B_7") (pintype "input"))
    )
    (net (code "15") (name "/SEGC") (class "Default")
      (node (ref "U1") (pin "32") (pinfunction "P0.5_32") (pintype "unspecified"))
      (node (ref "U3") (pin "4") (pinfunction "C_4") (pintype "input"))
    )
    (net (code "16") (name "/SEGD") (class "Default")
      (node (ref "U1") (pin "33") (pinfunction "P0.4_33") (pintype "unspecified"))
      (node (ref "U3") (pin "2") (pinfunction "D_2") (pintype "input"))
    )
    (net (code "17") (name "/SEGDP") (class "Default")
      (node (ref "U1") (pin "37") (pinfunction "P0.0_37") (pintype "unspecified"))
      (node (ref "U3") (pin "3") (pinfunction "DP_3") (pintype "input"))
    )
    (net (code "18") (name "/SEGE") (class "Default")
      (node (ref "U1") (pin "34") (pinfunction "P0.3_34") (pintype "unspecified"))
      (node (ref "U3") (pin "1") (pinfunction "E_1") (pintype "input"))
    )
    (net (code "19") (name "/SEGF") (class "Default")
      (node (ref "U1") (pin "35") (pinfunction "P0.2_35") (pintype "unspecified"))
      (node (ref "U3") (pin "10") (pinfunction "F_10") (pintype "input"))
    )
    (net (code "20") (name "/SEGG") (class "Default")
      (node (ref "U1") (pin "36") (pinfunction "P0.1_36") (pintype "unspecified"))
      (node (ref "U3") (pin "5") (pinfunction "G_5") (pintype "input"))
    )
    (net (code "21") (name "/SEL0") (class "Default")
      (node (ref "R15") (pin "1") (pinfunction "1_1") (pintype "input"))
      (node (ref "U1") (pin "18") (pinfunction "P2.0_18") (pintype "unspecified"))
    )
    (net (code "22") (name "/SEL1") (class "Default")
      (node (ref "R16") (pin "1") (pinfunction "1_1") (pintype "input"))
      (node (ref "U1") (pin "19") (pinfunction "P2.1_19") (pintype "unspecified"))
    )
    (net (code "23") (name "/SEL2") (class "Default")
      (node (ref "R17") (pin "1") (pinfunction "1_1") (pintype "input"))
      (node (ref "U1") (pin "20") (pinfunction "P2.2_20") (pintype "unspecified"))
    )
    (net (code "24") (name "/SEL3") (class "Default")
      (node (ref "R18") (pin "1") (pinfunction "1_1") (pintype "input"))
      (node (ref "U1") (pin "21") (pinfunction "P2.3_21") (pintype "unspecified"))
    )
    (net (code "25") (name "/TXD") (class "Default")
      (node (ref "R33") (pin "1") (pinfunction "1_1") (pintype "input"))
      (node (ref "TXD") (pin "1") (pinfunction "Pin1_1") (pintype "input"))
      (node (ref "U2") (pin "7") (pinfunction "RXD_7") (pintype "unspecified"))
    )
    (net (code "26") (name "GND") (class "Default")
      (node (ref "C1") (pin "2") (pinfunction "2_2") (pintype "input"))
      (node (ref "C10") (pin "2") (pinfunction "2_2") (pintype "input"))
      (node (ref "C11") (pin "2") (pinfunction "2_2") (pintype "input"))
      (node (ref "C3") (pin "2") (pinfunction "2_2") (pintype "unspecified"))
      (node (ref "C4") (pin "2") (pinfunction "2_2") (pintype "unspecified"))
      (node (ref "C5") (pin "1") (pinfunction "1_1") (pintype "unspecified"))
      (node (ref "C6") (pin "1") (pinfunction "1_1") (pintype "unspecified"))
      (node (ref "C7") (pin "1") (pinfunction "1_1") (pintype "unspecified"))
      (node (ref "C8") (pin "2") (pinfunction "2_2") (pintype "input"))
      (node (ref "C9") (pin "2") (pinfunction "2_2") (pintype "input"))
      (node (ref "ESD1") (pin "1") (pinfunction "1_1") (pintype "unspecified"))
      (node (ref "GND") (pin "1") (pinfunction "Pin1_1") (pintype "input"))
      (node (ref "KEY1") (pin "3") (pinfunction "3_3") (pintype "input"))
      (node (ref "KEY2") (pin "3") (pinfunction "3_3") (pintype "input"))
      (node (ref "KEY3") (pin "3") (pinfunction "3_3") (pintype "input"))
      (node (ref "PLED") (pin "2") (pinfunction "-_2") (pintype "unspecified"))
      (node (ref "R25") (pin "2") (pinfunction "2_2") (pintype "input"))
      (node (ref "R27") (pin "2") (pinfunction "2_2") (pintype "unspecified"))
      (node (ref "R29") (pin "2") (pinfunction "2_2") (pintype "input"))
      (node (ref "R8") (pin "1") (pinfunction "1_1") (pintype "input"))
      (node (ref "R9") (pin "1") (pinfunction "1_1") (pintype "input"))
      (node (ref "T1") (pin "1") (pinfunction "1_1") (pintype "input"))
      (node (ref "T2") (pin "1") (pinfunction "1_1") (pintype "input"))
      (node (ref "T3") (pin "1") (pinfunction "1_1") (pintype "input"))
      (node (ref "T4") (pin "1") (pinfunction "1_1") (pintype "input"))
      (node (ref "U2") (pin "3") (pinfunction "GND_3") (pintype "unspecified"))
      (node (ref "USB") (pin "0") (pinfunction "SH_0") (pintype "unspecified"))
      (node (ref "USB") (pin "1") (pinfunction "SH_1") (pintype "unspecified"))
      (node (ref "USB") (pin "2") (pinfunction "SH_2") (pintype "unspecified"))
      (node (ref "USB") (pin "3") (pinfunction "SH_3") (pintype "unspecified"))
      (node (ref "USB") (pin "A1") (pinfunction "GND_A1") (pintype "unspecified"))
      (node (ref "USB") (pin "A12") (pinfunction "GND_A12") (pintype "unspecified"))
      (node (ref "USB") (pin "B1") (pinfunction "GND_B1") (pintype "unspecified"))
      (node (ref "USB") (pin "B12") (pinfunction "GND_B12") (pintype "unspecified"))
    )
    (net (code "27") (name "Net-(BEEP-+)") (class "Default")
      (node (ref "BEEP") (pin "1") (pinfunction "+_1") (pintype "unspecified"))
      (node (ref "Q5") (pin "3") (pinfunction "C_3") (pintype "input"))
    )
    (net (code "28") (name "Net-(BEEP-Pad2)") (class "Default")
      (node (ref "BEEP") (pin "2") (pinfunction "2_2") (pintype "unspecified"))
      (node (ref "R29") (pin "1") (pinfunction "1_1") (pintype "input"))
    )
    (net (code "29") (name "Net-(D1-A)") (class "Default")
      (node (ref "D1") (pin "2") (pinfunction "A_2") (pintype "unspecified"))
      (node (ref "USB") (pin "A4") (pinfunction "VBUS_A4") (pintype "unspecified"))
      (node (ref "USB") (pin "A9") (pinfunction "VBUS_A9") (pintype "unspecified"))
      (node (ref "USB") (pin "B4") (pinfunction "VBUS_B4") (pintype "unspecified"))
      (node (ref "USB") (pin "B9") (pinfunction "VBUS_B9") (pintype "unspecified"))
    )
    (net (code "30") (name "Net-(LED1-K)") (class "Default")
      (node (ref "LED1") (pin "2") (pinfunction "K_2") (pintype "unspecified"))
      (node (ref "R1") (pin "2") (pinfunction "2_2") (pintype "input"))
    )
    (net (code "31") (name "Net-(LED2-K)") (class "Default")
      (node (ref "LED2") (pin "2") (pinfunction "K_2") (pintype "unspecified"))
      (node (ref "R2") (pin "2") (pinfunction "2_2") (pintype "input"))
    )
    (net (code "32") (name "Net-(LED3-K)") (class "Default")
      (node (ref "LED3") (pin "2") (pinfunction "K_2") (pintype "unspecified"))
      (node (ref "R3") (pin "2") (pinfunction "2_2") (pintype "input"))
    )
    (net (code "33") (name "Net-(LED4-K)") (class "Default")
      (node (ref "LED4") (pin "2") (pinfunction "K_2") (pintype "unspecified"))
      (node (ref "R4") (pin "2") (pinfunction "2_2") (pintype "input"))
    )
    (net (code "34") (name "Net-(PLED-+)") (class "Default")
      (node (ref "PLED") (pin "1") (pinfunction "+_1") (pintype "unspecified"))
      (node (ref "R28") (pin "1") (pinfunction "1_1") (pintype "input"))
    )
    (net (code "35") (name "Net-(Q1-D)") (class "Default")
      (node (ref "Q1") (pin "3") (pinfunction "D_3") (pintype "unspecified"))
      (node (ref "R21") (pin "2") (pinfunction "2_2") (pintype "input"))
    )
    (net (code "36") (name "Net-(Q1-G)") (class "Default")
      (node (ref "Q1") (pin "1") (pinfunction "G_1") (pintype "unspecified"))
      (node (ref "R11") (pin "1") (pinfunction "1_1") (pintype "input"))
      (node (ref "R15") (pin "2") (pinfunction "2_2") (pintype "input"))
    )
    (net (code "37") (name "Net-(Q1-S)") (class "Default")
      (node (ref "Q1") (pin "2") (pinfunction "S_2") (pintype "unspecified"))
      (node (ref "R11") (pin "2") (pinfunction "2_2") (pintype "input"))
    )
    (net (code "38") (name "Net-(Q2-D)") (class "Default")
      (node (ref "Q2") (pin "3") (pinfunction "D_3") (pintype "unspecified"))
      (node (ref "R22") (pin "2") (pinfunction "2_2") (pintype "input"))
    )
    (net (code "39") (name "Net-(Q2-G)") (class "Default")
      (node (ref "Q2") (pin "1") (pinfunction "G_1") (pintype "unspecified"))
      (node (ref "R12") (pin "1") (pinfunction "1_1") (pintype "input"))
      (node (ref "R16") (pin "2") (pinfunction "2_2") (pintype "input"))
    )
    (net (code "40") (name "Net-(Q2-S)") (class "Default")
      (node (ref "Q2") (pin "2") (pinfunction "S_2") (pintype "unspecified"))
      (node (ref "R12") (pin "2") (pinfunction "2_2") (pintype "input"))
    )
    (net (code "41") (name "Net-(Q3-D)") (class "Default")
      (node (ref "Q3") (pin "3") (pinfunction "D_3") (pintype "unspecified"))
      (node (ref "R23") (pin "2") (pinfunction "2_2") (pintype "input"))
    )
    (net (code "42") (name "Net-(Q3-G)") (class "Default")
      (node (ref "Q3") (pin "1") (pinfunction "G_1") (pintype "unspecified"))
      (node (ref "R13") (pin "1") (pinfunction "1_1") (pintype "input"))
      (node (ref "R17") (pin "2") (pinfunction "2_2") (pintype "input"))
    )
    (net (code "43") (name "Net-(Q3-S)") (class "Default")
      (node (ref "Q3") (pin "2") (pinfunction "S_2") (pintype "unspecified"))
      (node (ref "R13") (pin "2") (pinfunction "2_2") (pintype "input"))
    )
    (net (code "44") (name "Net-(Q4-D)") (class "Default")
      (node (ref "Q4") (pin "3") (pinfunction "D_3") (pintype "unspecified"))
      (node (ref "R24") (pin "2") (pinfunction "2_2") (pintype "input"))
    )
    (net (code "45") (name "Net-(Q4-G)") (class "Default")
      (node (ref "Q4") (pin "1") (pinfunction "G_1") (pintype "unspecified"))
      (node (ref "R14") (pin "1") (pinfunction "1_1") (pintype "input"))
      (node (ref "R18") (pin "2") (pinfunction "2_2") (pintype "input"))
    )
    (net (code "46") (name "Net-(Q4-S)") (class "Default")
      (node (ref "Q4") (pin "2") (pinfunction "S_2") (pintype "unspecified"))
      (node (ref "R14") (pin "2") (pinfunction "2_2") (pintype "input"))
    )
    (net (code "47") (name "Net-(Q5-B)") (class "Default")
      (node (ref "Q5") (pin "2") (pinfunction "B_2") (pintype "input"))
      (node (ref "R19") (pin "2") (pinfunction "2_2") (pintype "input"))
      (node (ref "R20") (pin "1") (pinfunction "1_1") (pintype "input"))
    )
    (net (code "48") (name "Net-(Q5-E)") (class "Default")
      (node (ref "J1") (pin "2") (pinfunction "2_2") (pintype "input"))
      (node (ref "Q5") (pin "1") (pinfunction "E_1") (pintype "input"))
      (node (ref "R20") (pin "2") (pinfunction "2_2") (pintype "input"))
    )
    (net (code "49") (name "Net-(R26-Pad2)") (class "Default")
      (node (ref "R26") (pin "2") (pinfunction "2_2") (pintype "input"))
      (node (ref "RST") (pin "1") (pinfunction "1_1") (pintype "input"))
    )
    (net (code "50") (name "Net-(U1-EA#{slash}P4.6)") (class "Default")
      (node (ref "R10") (pin "2") (pinfunction "2_2") (pintype "input"))
      (node (ref "U1") (pin "29") (pinfunction "EA#/P4.6_29") (pintype "unspecified"))
    )
    (net (code "51") (name "Net-(U1-P3.7{slash}RD#)") (class "Default")
      (node (ref "C14") (pin "1") (pinfunction "1_1") (pintype "unspecified"))
      (node (ref "R34") (pin "1") (pinfunction "1_1") (pintype "input"))
      (node (ref "U1") (pin "13") (pinfunction "P3.7/RD#_13") (pintype "unspecified"))
      (node (ref "X2") (pin "1") (pinfunction "OSC1_1") (pintype "unspecified"))
    )
    (net (code "52") (name "Net-(U1-RXD{slash}P3.0)") (class "Default")
      (node (ref "R33") (pin "2") (pinfunction "2_2") (pintype "input"))
      (node (ref "U1") (pin "5") (pinfunction "RXD/P3.0_5") (pintype "unspecified"))
    )
    (net (code "53") (name "Net-(U1-TXD{slash}P3.1)") (class "Default")
      (node (ref "R32") (pin "2") (pinfunction "2_2") (pintype "input"))
      (node (ref "U1") (pin "7") (pinfunction "TXD/P3.1_7") (pintype "unspecified"))
    )
    (net (code "54") (name "Net-(U1-XTAL1)") (class "Default")
      (node (ref "C13") (pin "2") (pinfunction "2_2") (pintype "unspecified"))
      (node (ref "C14") (pin "2") (pinfunction "2_2") (pintype "unspecified"))
      (node (ref "U1") (pin "15") (pinfunction "XTAL1_15") (pintype "unspecified"))
      (node (ref "X2") (pin "2") (pinfunction "GND_2") (pintype "unspecified"))
      (node (ref "X2") (pin "4") (pinfunction "GND_4") (pintype "unspecified"))
    )
    (net (code "55") (name "Net-(U1-XTAL2)") (class "Default")
      (node (ref "C13") (pin "1") (pinfunction "1_1") (pintype "unspecified"))
      (node (ref "R34") (pin "2") (pinfunction "2_2") (pintype "input"))
      (node (ref "U1") (pin "14") (pinfunction "XTAL2_14") (pintype "unspecified"))
      (node (ref "X2") (pin "3") (pinfunction "OSC2_3") (pintype "unspecified"))
    )
    (net (code "56") (name "Net-(U2-V3)") (class "Default")
      (node (ref "C3") (pin "1") (pinfunction "1_1") (pintype "unspecified"))
      (node (ref "U2") (pin "8") (pinfunction "V3_8") (pintype "unspecified"))
    )
    (net (code "57") (name "Net-(U3-DIG1)") (class "Default")
      (node (ref "R21") (pin "1") (pinfunction "1_1") (pintype "input"))
      (node (ref "U3") (pin "12") (pinfunction "DIG1_12") (pintype "input"))
    )
    (net (code "58") (name "Net-(U3-DIG2)") (class "Default")
      (node (ref "R22") (pin "1") (pinfunction "1_1") (pintype "input"))
      (node (ref "U3") (pin "9") (pinfunction "DIG2_9") (pintype "input"))
    )
    (net (code "59") (name "Net-(U3-DIG3)") (class "Default")
      (node (ref "R23") (pin "1") (pinfunction "1_1") (pintype "input"))
      (node (ref "U3") (pin "8") (pinfunction "DIG3_8") (pintype "input"))
    )
    (net (code "60") (name "Net-(U3-DIG4)") (class "Default")
      (node (ref "R24") (pin "1") (pinfunction "1_1") (pintype "input"))
      (node (ref "U3") (pin "6") (pinfunction "DIG4_6") (pintype "input"))
    )
    (net (code "61") (name "Net-(USB-CC1)") (class "Default")
      (node (ref "R9") (pin "2") (pinfunction "2_2") (pintype "input"))
      (node (ref "USB") (pin "A5") (pinfunction "CC1_A5") (pintype "unspecified"))
    )
    (net (code "62") (name "Net-(USB-CC2)") (class "Default")
      (node (ref "R8") (pin "2") (pinfunction "2_2") (pintype "input"))
      (node (ref "USB") (pin "B5") (pinfunction "CC2_B5") (pintype "unspecified"))
    )
    (net (code "63") (name "USB_IN") (class "Default")
      (node (ref "C1") (pin "1") (pinfunction "1_1") (pintype "input"))
      (node (ref "C4") (pin "1") (pinfunction "1_1") (pintype "unspecified"))
      (node (ref "D1") (pin "1") (pinfunction "K_1") (pintype "unspecified"))
      (node (ref "ESD1") (pin "2") (pinfunction "2_2") (pintype "unspecified"))
      (node (ref "PowerKey") (pin "1") (pinfunction "1_1") (pintype "unspecified"))
      (node (ref "PowerKey") (pin "2") (pinfunction "2_2") (pintype "unspecified"))
      (node (ref "PowerKey") (pin "4") (pinfunction "4_4") (pintype "unspecified"))
      (node (ref "PowerKey") (pin "5") (pinfunction "5_5") (pintype "unspecified"))
      (node (ref "R27") (pin "1") (pinfunction "1_1") (pintype "unspecified"))
      (node (ref "U2") (pin "5") (pinfunction "VCC_5") (pintype "unspecified"))
      (node (ref "USB_IN") (pin "1") (pinfunction "Pin1_1") (pintype "input"))
    )
    (net (code "64") (name "VCC") (class "Default")
      (node (ref "C10") (pin "1") (pinfunction "1_1") (pintype "input"))
      (node (ref "C11") (pin "1") (pinfunction "1_1") (pintype "input"))
      (node (ref "C12") (pin "2") (pinfunction "2_2") (pintype "input"))
      (node (ref "C8") (pin "1") (pinfunction "1_1") (pintype "input"))
      (node (ref "C9") (pin "1") (pinfunction "1_1") (pintype "input"))
      (node (ref "J1") (pin "1") (pinfunction "1_1") (pintype "input"))
      (node (ref "LED1") (pin "1") (pinfunction "A_1") (pintype "unspecified"))
      (node (ref "LED2") (pin "1") (pinfunction "A_1") (pintype "unspecified"))
      (node (ref "LED3") (pin "1") (pinfunction "A_1") (pintype "unspecified"))
      (node (ref "LED4") (pin "1") (pinfunction "A_1") (pintype "unspecified"))
      (node (ref "PowerKey") (pin "3") (pinfunction "3_3") (pintype "unspecified"))
      (node (ref "PowerKey") (pin "6") (pinfunction "6_6") (pintype "unspecified"))
      (node (ref "R10") (pin "1") (pinfunction "1_1") (pintype "input"))
      (node (ref "R28") (pin "2") (pinfunction "2_2") (pintype "input"))
      (node (ref "R5") (pin "2") (pinfunction "2_2") (pintype "input"))
      (node (ref "R6") (pin "2") (pinfunction "2_2") (pintype "input"))
      (node (ref "R7") (pin "2") (pinfunction "2_2") (pintype "input"))
      (node (ref "RST") (pin "2") (pinfunction "2_2") (pintype "input"))
      (node (ref "U1") (pin "38") (pinfunction "VCC_38") (pintype "unspecified"))
      (node (ref "VCC") (pin "1") (pinfunction "Pin1_1") (pintype "input"))
    )
    (net (code "65") (name "unconnected-(KEY1-Pad2)") (class "Default")
      (node (ref "KEY1") (pin "2") (pinfunction "2_2") (pintype "input+no_connect"))
    )
    (net (code "66") (name "unconnected-(KEY1-Pad4)") (class "Default")
      (node (ref "KEY1") (pin "4") (pinfunction "4_4") (pintype "input+no_connect"))
    )
    (net (code "67") (name "unconnected-(KEY2-Pad2)") (class "Default")
      (node (ref "KEY2") (pin "2") (pinfunction "2_2") (pintype "input+no_connect"))
    )
    (net (code "68") (name "unconnected-(KEY2-Pad4)") (class "Default")
      (node (ref "KEY2") (pin "4") (pinfunction "4_4") (pintype "input+no_connect"))
    )
    (net (code "69") (name "unconnected-(KEY3-Pad2)") (class "Default")
      (node (ref "KEY3") (pin "2") (pinfunction "2_2") (pintype "input+no_connect"))
    )
    (net (code "70") (name "unconnected-(KEY3-Pad4)") (class "Default")
      (node (ref "KEY3") (pin "4") (pinfunction "4_4") (pintype "input+no_connect"))
    )
    (net (code "71") (name "unconnected-(U1-ALE{slash}P4.5-Pad27)") (class "Default")
      (node (ref "U1") (pin "27") (pinfunction "ALE/P4.5_27") (pintype "unspecified+no_connect"))
    )
    (net (code "72") (name "unconnected-(U1-GND-Pad16)") (class "Default")
      (node (ref "U1") (pin "16") (pinfunction "GND_16") (pintype "unspecified+no_connect"))
    )
    (net (code "73") (name "unconnected-(U1-P1.1{slash}T2EX-Pad41)") (class "Default")
      (node (ref "U1") (pin "41") (pinfunction "P1.1/T2EX_41") (pintype "unspecified+no_connect"))
    )
    (net (code "74") (name "unconnected-(U1-P1.2-Pad42)") (class "Default")
      (node (ref "U1") (pin "42") (pinfunction "P1.2_42") (pintype "unspecified+no_connect"))
    )
    (net (code "75") (name "unconnected-(U1-P1.3-Pad43)") (class "Default")
      (node (ref "U1") (pin "43") (pinfunction "P1.3_43") (pintype "unspecified+no_connect"))
    )
    (net (code "76") (name "unconnected-(U1-P1.4-Pad44)") (class "Default")
      (node (ref "U1") (pin "44") (pinfunction "P1.4_44") (pintype "unspecified+no_connect"))
    )
    (net (code "77") (name "unconnected-(U1-P1.5-Pad1)") (class "Default")
      (node (ref "U1") (pin "1") (pinfunction "P1.5_1") (pintype "unspecified+no_connect"))
    )
    (net (code "78") (name "unconnected-(U1-P1.6-Pad2)") (class "Default")
      (node (ref "U1") (pin "2") (pinfunction "P1.6_2") (pintype "unspecified+no_connect"))
    )
    (net (code "79") (name "unconnected-(U1-P1.7-Pad3)") (class "Default")
      (node (ref "U1") (pin "3") (pinfunction "P1.7_3") (pintype "unspecified+no_connect"))
    )
    (net (code "80") (name "unconnected-(U1-P3.6{slash}WR#-Pad12)") (class "Default")
      (node (ref "U1") (pin "12") (pinfunction "P3.6/WR#_12") (pintype "unspecified+no_connect"))
    )
    (net (code "81") (name "unconnected-(U1-P4.0-Pad17)") (class "Default")
      (node (ref "U1") (pin "17") (pinfunction "P4.0_17") (pintype "unspecified+no_connect"))
    )
    (net (code "82") (name "unconnected-(U1-P4.1-Pad28)") (class "Default")
      (node (ref "U1") (pin "28") (pinfunction "P4.1_28") (pintype "unspecified+no_connect"))
    )
    (net (code "83") (name "unconnected-(U1-P4.2{slash}INT3#-Pad39)") (class "Default")
      (node (ref "U1") (pin "39") (pinfunction "P4.2/INT3#_39") (pintype "unspecified+no_connect"))
    )
    (net (code "84") (name "unconnected-(U1-P4.3{slash}INT2#-Pad6)") (class "Default")
      (node (ref "U1") (pin "6") (pinfunction "P4.3/INT2#_6") (pintype "unspecified+no_connect"))
    )
    (net (code "85") (name "unconnected-(U1-PSEN#{slash}P4.4-Pad26)") (class "Default")
      (node (ref "U1") (pin "26") (pinfunction "PSEN#/P4.4_26") (pintype "unspecified+no_connect"))
    )
    (net (code "86") (name "unconnected-(U1-T1{slash}P3.5-Pad11)") (class "Default")
      (node (ref "U1") (pin "11") (pinfunction "T1/P3.5_11") (pintype "unspecified+no_connect"))
    )
    (net (code "87") (name "unconnected-(U2-RTS#-Pad4)") (class "Default")
      (node (ref "U2") (pin "4") (pinfunction "RTS#_4") (pintype "unspecified+no_connect"))
    )
    (net (code "88") (name "unconnected-(USB-SBU1-PadA8)") (class "Default")
      (node (ref "USB") (pin "A8") (pinfunction "SBU1_A8") (pintype "unspecified+no_connect"))
    )
    (net (code "89") (name "unconnected-(USB-SBU2-PadB8)") (class "Default")
      (node (ref "USB") (pin "B8") (pinfunction "SBU2_B8") (pintype "unspecified+no_connect"))
    )
  )
)
